# RSD_M1_HELMET_UNIT_MCU_V2.net
KiCad netlist of a schematic drawn in Altium Designer
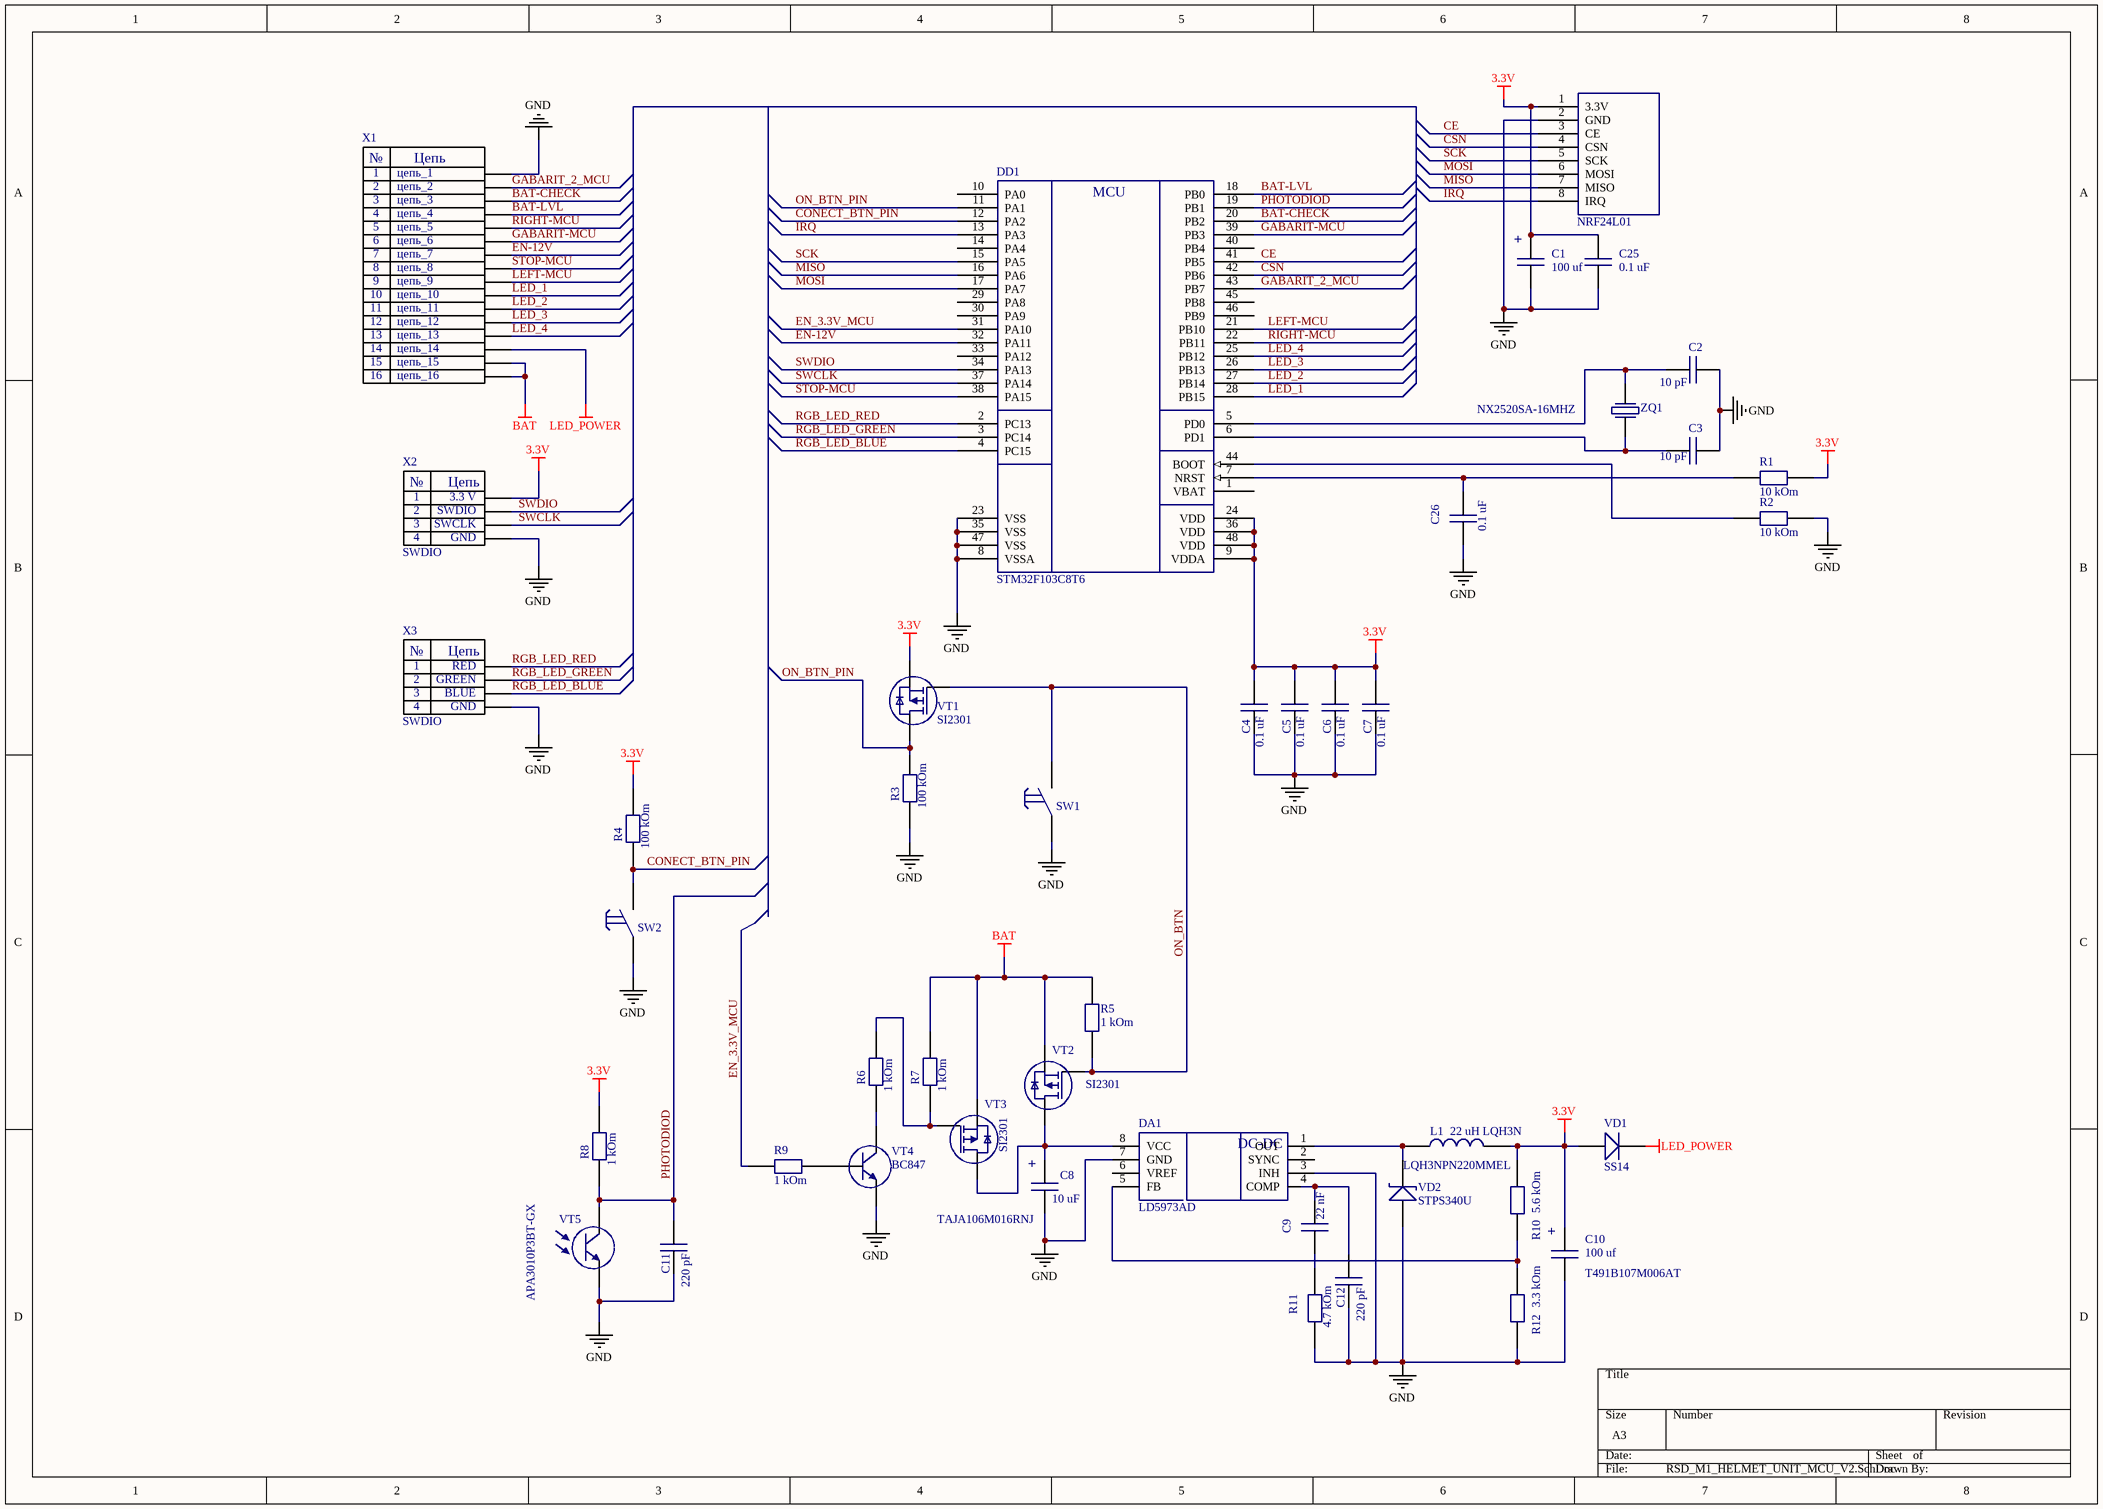
[diagram p0: RSD_M1_HELMET_UNIT_MCU_V2.SchDoc]

(export (version "E")
  (design (tool "Eeschema 10.0.6"))
  (components
    (comp (ref "C1")
      (value "100 uf")
      (footprint "tantal_case_B")
      (libsource (lib "my_library") (part "Capacitor_Polar"))
    )
    (comp (ref "C2")
      (value "10 pF")
      (footprint "CAP0603")
      (fields (field (name "Comment") "Capacitor"))
      (libsource (lib "my_library") (part "Capacitor"))
    )
    (comp (ref "C3")
      (value "10 pF")
      (footprint "CAP0603")
      (fields (field (name "Comment") "Capacitor"))
      (libsource (lib "my_library") (part "Capacitor"))
    )
    (comp (ref "C4")
      (value "0.1 uF")
      (footprint "CAP0603")
      (fields (field (name "Comment") "Capacitor"))
      (libsource (lib "my_library") (part "Capacitor"))
    )
    (comp (ref "C5")
      (value "0.1 uF")
      (footprint "CAP0603")
      (fields (field (name "Comment") "Capacitor"))
      (libsource (lib "my_library") (part "Capacitor"))
    )
    (comp (ref "C6")
      (value "0.1 uF")
      (footprint "CAP0603")
      (fields (field (name "Comment") "Capacitor"))
      (libsource (lib "my_library") (part "Capacitor"))
    )
    (comp (ref "C7")
      (value "0.1 uF")
      (footprint "CAP0603")
      (fields (field (name "Comment") "Capacitor"))
      (libsource (lib "my_library") (part "Capacitor"))
    )
    (comp (ref "C8")
      (value "10 uF")
      (footprint "tantal_case_A")
      (fields (field (name "ALTIUM_VALUE") "TAJA106M016RNJ"))
      (libsource (lib "my_library") (part "Capacitor_Polar"))
    )
    (comp (ref "C9")
      (value "22 nF")
      (footprint "CAP0603")
      (fields (field (name "Comment") "Capacitor"))
      (libsource (lib "my_library") (part "Capacitor"))
    )
    (comp (ref "C10")
      (value "100 uf")
      (footprint "tantal_case_B")
      (fields (field (name "ALTIUM_VALUE") "T491B107M006AT"))
      (libsource (lib "my_library") (part "Capacitor_Polar"))
    )
    (comp (ref "C11")
      (value "220 pF")
      (footprint "CAP0603")
      (fields (field (name "Comment") "Capacitor"))
      (libsource (lib "my_library") (part "Capacitor"))
    )
    (comp (ref "C12")
      (value "220 pF")
      (footprint "CAP0603")
      (fields (field (name "Comment") "Capacitor"))
      (libsource (lib "my_library") (part "Capacitor"))
    )
    (comp (ref "C25")
      (value "0.1 uF")
      (footprint "CAP0603")
      (fields (field (name "Comment") "Capacitor"))
      (libsource (lib "my_library") (part "Capacitor"))
    )
    (comp (ref "C26")
      (value "0.1 uF")
      (footprint "CAP0603")
      (fields (field (name "Comment") "Capacitor"))
      (libsource (lib "my_library") (part "Capacitor"))
    )
    (comp (ref "DA1")
      (value "LD5973AD")
      (footprint "SOIC-8")
      (libsource (lib "my_library") (part "LD5973AD"))
    )
    (comp (ref "DD1")
      (value "STM32F103C8T6")
      (footprint "STM32F103C8T6")
      (fields (field (name "Comment") "STM32F103C8Tx"))
      (libsource (lib "my_library") (part "STM32F103C8Tx"))
    )
    (comp (ref "L1")
      (value "22 uH LQH3N")
      (footprint "LQH3N")
      (fields (field (name "PN") "LQH3NPN220MMEL") (field (name "Comment") "coil"))
      (libsource (lib "my_library") (part "coil"))
    )
    (comp (ref "NRF1")
      (value "NRF24L01")
      (footprint "NRF24L01")
      (libsource (lib "my_library") (part "NRF24L01"))
    )
    (comp (ref "R1")
      (value "10 kOm")
      (footprint "Res0603")
      (fields (field (name "Comment") "Resistor"))
      (libsource (lib "my_library") (part "Resistor"))
    )
    (comp (ref "R2")
      (value "10 kOm")
      (footprint "Res0603")
      (fields (field (name "Comment") "Resistor"))
      (libsource (lib "my_library") (part "Resistor"))
    )
    (comp (ref "R3")
      (value "100 kOm")
      (footprint "Res0603")
      (fields (field (name "Comment") "Resistor"))
      (libsource (lib "my_library") (part "Resistor"))
    )
    (comp (ref "R4")
      (value "100 kOm")
      (footprint "Res0603")
      (fields (field (name "Comment") "Resistor"))
      (libsource (lib "my_library") (part "Resistor"))
    )
    (comp (ref "R5")
      (value "1 kOm")
      (footprint "Res0603")
      (fields (field (name "Comment") "Resistor"))
      (libsource (lib "my_library") (part "Resistor"))
    )
    (comp (ref "R6")
      (value "1 kOm")
      (footprint "Res0603")
      (fields (field (name "Comment") "Resistor"))
      (libsource (lib "my_library") (part "Resistor"))
    )
    (comp (ref "R7")
      (value "1 kOm")
      (footprint "Res0603")
      (fields (field (name "Comment") "Resistor"))
      (libsource (lib "my_library") (part "Resistor"))
    )
    (comp (ref "R8")
      (value "1 kOm")
      (footprint "Res0603")
      (fields (field (name "Comment") "Resistor"))
      (libsource (lib "my_library") (part "Resistor"))
    )
    (comp (ref "R9")
      (value "1 kOm")
      (footprint "Res0603")
      (fields (field (name "Comment") "Resistor"))
      (libsource (lib "my_library") (part "Resistor"))
    )
    (comp (ref "R10")
      (value "5.6 kOm")
      (footprint "Res0603")
      (fields (field (name "Comment") "Resistor"))
      (libsource (lib "my_library") (part "Resistor"))
    )
    (comp (ref "R11")
      (value "4.7 kOm")
      (footprint "Res0603")
      (fields (field (name "Comment") "Resistor"))
      (libsource (lib "my_library") (part "Resistor"))
    )
    (comp (ref "R12")
      (value "3.3 kOm")
      (footprint "Res0603")
      (fields (field (name "Comment") "Resistor"))
      (libsource (lib "my_library") (part "Resistor"))
    )
    (comp (ref "SW1")
      (value "tact_switch")
      (footprint "tact_switch")
      (libsource (lib "my_library") (part "tact_switch"))
    )
    (comp (ref "SW2")
      (value "tact_switch")
      (footprint "tact_switch")
      (libsource (lib "my_library") (part "tact_switch"))
    )
    (comp (ref "VD1")
      (value "SS14")
      (footprint "SMA-F")
      (fields (field (name "Comment") "Diode"))
      (libsource (lib "my_library") (part "Diode"))
    )
    (comp (ref "VD2")
      (value "STPS340U")
      (footprint "SMB1")
      (fields (field (name "Comment") "Schottky"))
      (libsource (lib "my_library") (part "Schottky"))
    )
    (comp (ref "VT1")
      (value "SI2301")
      (footprint "SOT 23")
      (fields (field (name "Comment") "MOSFET-P"))
      (libsource (lib "my_library") (part "MOSFET-P"))
    )
    (comp (ref "VT2")
      (value "SI2301")
      (footprint "SOT 23")
      (fields (field (name "Comment") "MOSFET-P"))
      (libsource (lib "my_library") (part "MOSFET-P"))
    )
    (comp (ref "VT3")
      (value "SI2301")
      (footprint "SOT 23")
      (fields (field (name "Comment") "MOSFET-P"))
      (libsource (lib "my_library") (part "MOSFET-P"))
    )
    (comp (ref "VT4")
      (value "BC847")
      (footprint "SOT 23")
      (fields (field (name "Comment") "NPN"))
      (libsource (lib "my_library") (part "NPN"))
    )
    (comp (ref "VT5")
      (value "APA3010P3BT-GX")
      (footprint "LED0805")
      (fields (field (name "Comment") "Phototransistor"))
      (libsource (lib "my_library") (part "Phototransistor"))
    )
    (comp (ref "X1")
      (value "FPC_connector_16")
      (footprint "FPC_16_0.5")
      (fields
        (field (name "16") "цепь_16")
        (field (name "1") "цепь_1")
        (field (name "2") "цепь_2")
        (field (name "3") "цепь_3")
        (field (name "4") "цепь_4")
        (field (name "5") "цепь_5")
        (field (name "6") "цепь_6")
        (field (name "7") "цепь_7")
        (field (name "8") "цепь_8")
        (field (name "9") "цепь_9")
        (field (name "10") "цепь_10")
        (field (name "11") "цепь_11")
        (field (name "12") "цепь_12")
        (field (name "13") "цепь_13")
        (field (name "14") "цепь_14")
        (field (name "15") "цепь_15")
      )
      (libsource (lib "my_library") (part "FPC_connector_16"))
    )
    (comp (ref "X2")
      (value "SWDIO")
      (footprint "SWDIO")
      (fields
        (field (name "1") "3.3 V")
        (field (name "2") "SWDIO")
        (field (name "3") "SWCLK")
        (field (name "4") "GND")
      )
      (libsource (lib "my_library") (part "SWDIO"))
    )
    (comp (ref "X3")
      (value "SWDIO")
      (footprint "SWDIO")
      (fields
        (field (name "1") "RED")
        (field (name "2") "GREEN")
        (field (name "3") "BLUE")
        (field (name "4") "GND")
      )
      (libsource (lib "my_library") (part "SWDIO"))
    )
    (comp (ref "ZQ1")
      (value "NX2520SA-16MHZ")
      (footprint "crystal")
      (fields (field (name "Comment") "Qartz"))
      (libsource (lib "my_library") (part "Qartz"))
    )
  )
  (nets
    (net (code "1") (name "/BAT-CHECK") (class "Default")
      (node (ref "DD1") (pin "20") (pinfunction "PB2_20") (pintype "passive"))
      (node (ref "X1") (pin "3") (pinfunction "3_3") (pintype "passive"))
    )
    (net (code "2") (name "/BAT-LVL") (class "Default")
      (node (ref "DD1") (pin "18") (pinfunction "PB0_18") (pintype "passive"))
      (node (ref "X1") (pin "4") (pinfunction "4_4") (pintype "passive"))
    )
    (net (code "3") (name "/CE") (class "Default")
      (node (ref "DD1") (pin "41") (pinfunction "PB5_41") (pintype "passive"))
      (node (ref "NRF1") (pin "3") (pinfunction "CE_3") (pintype "passive"))
    )
    (net (code "4") (name "/CONECT_BTN_PIN") (class "Default")
      (node (ref "DD1") (pin "12") (pinfunction "PA2_12") (pintype "passive"))
      (node (ref "R4") (pin "2") (pinfunction "2_2") (pintype "passive"))
      (node (ref "SW2") (pin "2") (pinfunction "2_2") (pintype "passive"))
    )
    (net (code "5") (name "/CSN") (class "Default")
      (node (ref "DD1") (pin "42") (pinfunction "PB6_42") (pintype "passive"))
      (node (ref "NRF1") (pin "4") (pinfunction "CSN_4") (pintype "passive"))
    )
    (net (code "6") (name "/EN-12V") (class "Default")
      (node (ref "DD1") (pin "32") (pinfunction "PA11_32") (pintype "passive"))
      (node (ref "X1") (pin "7") (pinfunction "7_7") (pintype "passive"))
    )
    (net (code "7") (name "/EN_3.3V_MCU") (class "Default")
      (node (ref "DD1") (pin "31") (pinfunction "PA10_31") (pintype "passive"))
      (node (ref "R9") (pin "2") (pinfunction "2_2") (pintype "passive"))
    )
    (net (code "8") (name "/GABARIT-MCU") (class "Default")
      (node (ref "DD1") (pin "39") (pinfunction "PB3_39") (pintype "passive"))
      (node (ref "X1") (pin "6") (pinfunction "6_6") (pintype "passive"))
    )
    (net (code "9") (name "/GABARIT_2_MCU") (class "Default")
      (node (ref "DD1") (pin "43") (pinfunction "PB7_43") (pintype "passive"))
      (node (ref "X1") (pin "2") (pinfunction "2_2") (pintype "passive"))
    )
    (net (code "10") (name "/IRQ") (class "Default")
      (node (ref "DD1") (pin "13") (pinfunction "PA3_13") (pintype "passive"))
      (node (ref "NRF1") (pin "8") (pinfunction "IRQ_8") (pintype "passive"))
    )
    (net (code "11") (name "/LED_1") (class "Default")
      (node (ref "DD1") (pin "28") (pinfunction "PB15_28") (pintype "passive"))
      (node (ref "X1") (pin "10") (pinfunction "10_10") (pintype "passive"))
    )
    (net (code "12") (name "/LED_2") (class "Default")
      (node (ref "DD1") (pin "27") (pinfunction "PB14_27") (pintype "passive"))
      (node (ref "X1") (pin "11") (pinfunction "11_11") (pintype "passive"))
    )
    (net (code "13") (name "/LED_3") (class "Default")
      (node (ref "DD1") (pin "26") (pinfunction "PB13_26") (pintype "passive"))
      (node (ref "X1") (pin "12") (pinfunction "12_12") (pintype "passive"))
    )
    (net (code "14") (name "/LED_4") (class "Default")
      (node (ref "DD1") (pin "25") (pinfunction "PB12_25") (pintype "passive"))
      (node (ref "X1") (pin "13") (pinfunction "13_13") (pintype "passive"))
    )
    (net (code "15") (name "/LEFT-MCU") (class "Default")
      (node (ref "DD1") (pin "21") (pinfunction "PB10_21") (pintype "passive"))
      (node (ref "X1") (pin "9") (pinfunction "9_9") (pintype "passive"))
    )
    (net (code "16") (name "/MISO") (class "Default")
      (node (ref "DD1") (pin "16") (pinfunction "PA6_16") (pintype "passive"))
      (node (ref "NRF1") (pin "7") (pinfunction "MISO_7") (pintype "passive"))
    )
    (net (code "17") (name "/MOSI") (class "Default")
      (node (ref "DD1") (pin "17") (pinfunction "PA7_17") (pintype "passive"))
      (node (ref "NRF1") (pin "6") (pinfunction "MOSI_6") (pintype "passive"))
    )
    (net (code "18") (name "/ON_BTN") (class "Default")
      (node (ref "R5") (pin "1") (pinfunction "1_1") (pintype "passive"))
      (node (ref "SW1") (pin "2") (pinfunction "2_2") (pintype "passive"))
      (node (ref "VT1") (pin "G") (pintype "passive"))
      (node (ref "VT2") (pin "G") (pintype "passive"))
    )
    (net (code "19") (name "/ON_BTN_PIN") (class "Default")
      (node (ref "DD1") (pin "11") (pinfunction "PA1_11") (pintype "passive"))
      (node (ref "R3") (pin "1") (pinfunction "1_1") (pintype "passive"))
      (node (ref "VT1") (pin "D") (pintype "passive"))
    )
    (net (code "20") (name "/PHOTODIOD") (class "Default")
      (node (ref "C11") (pin "2") (pinfunction "2_2") (pintype "passive"))
      (node (ref "DD1") (pin "19") (pinfunction "PB1_19") (pintype "passive"))
      (node (ref "R8") (pin "1") (pinfunction "1_1") (pintype "passive"))
      (node (ref "VT5") (pin "1") (pinfunction "1_1") (pintype "passive"))
    )
    (net (code "21") (name "/RGB_LED_BLUE") (class "Default")
      (node (ref "DD1") (pin "4") (pinfunction "PC15_4") (pintype "passive"))
      (node (ref "X3") (pin "3") (pinfunction "3_3") (pintype "passive"))
    )
    (net (code "22") (name "/RGB_LED_GREEN") (class "Default")
      (node (ref "DD1") (pin "3") (pinfunction "PC14_3") (pintype "passive"))
      (node (ref "X3") (pin "2") (pinfunction "2_2") (pintype "passive"))
    )
    (net (code "23") (name "/RGB_LED_RED") (class "Default")
      (node (ref "DD1") (pin "2") (pinfunction "PC13_2") (pintype "passive"))
      (node (ref "X3") (pin "1") (pinfunction "1_1") (pintype "passive"))
    )
    (net (code "24") (name "/RIGHT-MCU") (class "Default")
      (node (ref "DD1") (pin "22") (pinfunction "PB11_22") (pintype "passive"))
      (node (ref "X1") (pin "5") (pinfunction "5_5") (pintype "passive"))
    )
    (net (code "25") (name "/SCK") (class "Default")
      (node (ref "DD1") (pin "15") (pinfunction "PA5_15") (pintype "passive"))
      (node (ref "NRF1") (pin "5") (pinfunction "SCK_5") (pintype "passive"))
    )
    (net (code "26") (name "/STOP-MCU") (class "Default")
      (node (ref "DD1") (pin "38") (pinfunction "PA15_38") (pintype "passive"))
      (node (ref "X1") (pin "8") (pinfunction "8_8") (pintype "passive"))
    )
    (net (code "27") (name "/SWCLK") (class "Default")
      (node (ref "DD1") (pin "37") (pinfunction "PA14_37") (pintype "passive"))
      (node (ref "X2") (pin "3") (pinfunction "3_3") (pintype "passive"))
    )
    (net (code "28") (name "/SWDIO") (class "Default")
      (node (ref "DD1") (pin "34") (pinfunction "PA13_34") (pintype "passive"))
      (node (ref "X2") (pin "2") (pinfunction "2_2") (pintype "passive"))
    )
    (net (code "29") (name "3.3V") (class "Default")
      (node (ref "C1") (pin "1") (pinfunction "1_1") (pintype "passive"))
      (node (ref "C10") (pin "1") (pinfunction "1_1") (pintype "passive"))
      (node (ref "C25") (pin "2") (pinfunction "2_2") (pintype "passive"))
      (node (ref "C4") (pin "2") (pinfunction "2_2") (pintype "passive"))
      (node (ref "C5") (pin "2") (pinfunction "2_2") (pintype "passive"))
      (node (ref "C6") (pin "2") (pinfunction "2_2") (pintype "passive"))
      (node (ref "C7") (pin "2") (pinfunction "2_2") (pintype "passive"))
      (node (ref "DD1") (pin "24") (pinfunction "VDD_24") (pintype "passive"))
      (node (ref "DD1") (pin "36") (pinfunction "VDD_36") (pintype "passive"))
      (node (ref "DD1") (pin "48") (pinfunction "VDD_48") (pintype "passive"))
      (node (ref "DD1") (pin "9") (pinfunction "VDDA_9") (pintype "passive"))
      (node (ref "L1") (pin "2") (pinfunction "2_2") (pintype "passive"))
      (node (ref "NRF1") (pin "1") (pinfunction "3.3V_1") (pintype "passive"))
      (node (ref "R1") (pin "2") (pinfunction "2_2") (pintype "passive"))
      (node (ref "R10") (pin "1") (pinfunction "1_1") (pintype "passive"))
      (node (ref "R4") (pin "1") (pinfunction "1_1") (pintype "passive"))
      (node (ref "R8") (pin "2") (pinfunction "2_2") (pintype "passive"))
      (node (ref "VD1") (pin "2") (pinfunction "2_2") (pintype "passive"))
      (node (ref "VT1") (pin "S") (pintype "passive"))
      (node (ref "X2") (pin "1") (pinfunction "1_1") (pintype "passive"))
    )
    (net (code "30") (name "BAT") (class "Default")
      (node (ref "R5") (pin "2") (pinfunction "2_2") (pintype "passive"))
      (node (ref "R7") (pin "2") (pinfunction "2_2") (pintype "passive"))
      (node (ref "VT2") (pin "S") (pintype "passive"))
      (node (ref "VT3") (pin "S") (pintype "passive"))
      (node (ref "X1") (pin "15") (pinfunction "15_15") (pintype "passive"))
      (node (ref "X1") (pin "16") (pinfunction "16_16") (pintype "passive"))
    )
    (net (code "31") (name "GND") (class "Default")
      (node (ref "C1") (pin "2") (pinfunction "2_2") (pintype "passive"))
      (node (ref "C10") (pin "2") (pinfunction "2_2") (pintype "passive"))
      (node (ref "C11") (pin "1") (pinfunction "1_1") (pintype "passive"))
      (node (ref "C12") (pin "1") (pinfunction "1_1") (pintype "passive"))
      (node (ref "C2") (pin "1") (pinfunction "1_1") (pintype "passive"))
      (node (ref "C25") (pin "1") (pinfunction "1_1") (pintype "passive"))
      (node (ref "C26") (pin "1") (pinfunction "1_1") (pintype "passive"))
      (node (ref "C3") (pin "1") (pinfunction "1_1") (pintype "passive"))
      (node (ref "C4") (pin "1") (pinfunction "1_1") (pintype "passive"))
      (node (ref "C5") (pin "1") (pinfunction "1_1") (pintype "passive"))
      (node (ref "C6") (pin "1") (pinfunction "1_1") (pintype "passive"))
      (node (ref "C7") (pin "1") (pinfunction "1_1") (pintype "passive"))
      (node (ref "C8") (pin "2") (pinfunction "2_2") (pintype "passive"))
      (node (ref "DA1") (pin "3") (pinfunction "INH_3") (pintype "passive"))
      (node (ref "DA1") (pin "7") (pinfunction "GND_7") (pintype "passive"))
      (node (ref "DD1") (pin "23") (pinfunction "VSS_23") (pintype "passive"))
      (node (ref "DD1") (pin "35") (pinfunction "VSS_35") (pintype "passive"))
      (node (ref "DD1") (pin "47") (pinfunction "VSS_47") (pintype "passive"))
      (node (ref "DD1") (pin "8") (pinfunction "VSSA_8") (pintype "passive"))
      (node (ref "NRF1") (pin "2") (pinfunction "GND_2") (pintype "passive"))
      (node (ref "R11") (pin "2") (pinfunction "2_2") (pintype "passive"))
      (node (ref "R12") (pin "2") (pinfunction "2_2") (pintype "passive"))
      (node (ref "R2") (pin "2") (pinfunction "2_2") (pintype "passive"))
      (node (ref "R3") (pin "2") (pinfunction "2_2") (pintype "passive"))
      (node (ref "SW1") (pin "1") (pinfunction "1_1") (pintype "passive"))
      (node (ref "SW2") (pin "1") (pinfunction "1_1") (pintype "passive"))
      (node (ref "VD2") (pin "2") (pinfunction "2_2") (pintype "passive"))
      (node (ref "VT4") (pin "E") (pinfunction "E_E") (pintype "passive"))
      (node (ref "VT5") (pin "2") (pinfunction "2_2") (pintype "passive"))
      (node (ref "X1") (pin "1") (pinfunction "1_1") (pintype "passive"))
      (node (ref "X2") (pin "4") (pinfunction "4_4") (pintype "passive"))
      (node (ref "X3") (pin "4") (pinfunction "4_4") (pintype "passive"))
    )
    (net (code "32") (name "LED_POWER") (class "Default")
      (node (ref "VD1") (pin "1") (pinfunction "1_1") (pintype "passive"))
      (node (ref "X1") (pin "14") (pinfunction "14_14") (pintype "passive"))
    )
    (net (code "33") (name "Net-(C9-Pad1)") (class "Default")
      (node (ref "C9") (pin "1") (pinfunction "1_1") (pintype "passive"))
      (node (ref "R11") (pin "1") (pinfunction "1_1") (pintype "passive"))
    )
    (net (code "34") (name "Net-(DA1-COMP)") (class "Default")
      (node (ref "C12") (pin "2") (pinfunction "2_2") (pintype "passive"))
      (node (ref "C9") (pin "2") (pinfunction "2_2") (pintype "passive"))
      (node (ref "DA1") (pin "4") (pinfunction "COMP_4") (pintype "passive"))
    )
    (net (code "35") (name "Net-(DA1-FB)") (class "Default")
      (node (ref "DA1") (pin "5") (pinfunction "FB_5") (pintype "passive"))
      (node (ref "R10") (pin "2") (pinfunction "2_2") (pintype "passive"))
      (node (ref "R12") (pin "1") (pinfunction "1_1") (pintype "passive"))
    )
    (net (code "36") (name "Net-(DA1-OUT)") (class "Default")
      (node (ref "DA1") (pin "1") (pinfunction "OUT_1") (pintype "passive"))
      (node (ref "L1") (pin "1") (pinfunction "1_1") (pintype "passive"))
      (node (ref "VD2") (pin "1") (pinfunction "1_1") (pintype "passive"))
    )
    (net (code "37") (name "Net-(DA1-VCC)") (class "Default")
      (node (ref "C8") (pin "1") (pinfunction "1_1") (pintype "passive"))
      (node (ref "DA1") (pin "8") (pinfunction "VCC_8") (pintype "passive"))
      (node (ref "VT2") (pin "D") (pintype "passive"))
      (node (ref "VT3") (pin "D") (pintype "passive"))
    )
    (net (code "38") (name "Net-(DD1-BOOT)") (class "Default")
      (node (ref "DD1") (pin "44") (pinfunction "BOOT_44") (pintype "input"))
      (node (ref "R2") (pin "1") (pinfunction "1_1") (pintype "passive"))
    )
    (net (code "39") (name "Net-(DD1-NRST)") (class "Default")
      (node (ref "C26") (pin "2") (pinfunction "2_2") (pintype "passive"))
      (node (ref "DD1") (pin "7") (pinfunction "NRST_7") (pintype "input"))
      (node (ref "R1") (pin "1") (pinfunction "1_1") (pintype "passive"))
    )
    (net (code "40") (name "Net-(DD1-PD0)") (class "Default")
      (node (ref "C2") (pin "2") (pinfunction "2_2") (pintype "passive"))
      (node (ref "DD1") (pin "5") (pinfunction "PD0_5") (pintype "passive"))
      (node (ref "ZQ1") (pin "2") (pinfunction "2_2") (pintype "passive"))
    )
    (net (code "41") (name "Net-(DD1-PD1)") (class "Default")
      (node (ref "C3") (pin "2") (pinfunction "2_2") (pintype "passive"))
      (node (ref "DD1") (pin "6") (pinfunction "PD1_6") (pintype "passive"))
      (node (ref "ZQ1") (pin "1") (pinfunction "1_1") (pintype "passive"))
    )
    (net (code "42") (name "Net-(R6-Pad1)") (class "Default")
      (node (ref "R6") (pin "1") (pinfunction "1_1") (pintype "passive"))
      (node (ref "VT4") (pin "K") (pinfunction "K_K") (pintype "passive"))
    )
    (net (code "43") (name "Net-(R6-Pad2)") (class "Default")
      (node (ref "R6") (pin "2") (pinfunction "2_2") (pintype "passive"))
      (node (ref "R7") (pin "1") (pinfunction "1_1") (pintype "passive"))
      (node (ref "VT3") (pin "G") (pintype "passive"))
    )
    (net (code "44") (name "Net-(R9-Pad1)") (class "Default")
      (node (ref "R9") (pin "1") (pinfunction "1_1") (pintype "passive"))
      (node (ref "VT4") (pin "B") (pinfunction "B_B") (pintype "passive"))
    )
    (net (code "45") (name "unconnected-(DA1-SYNC-Pad2)") (class "Default")
      (node (ref "DA1") (pin "2") (pinfunction "SYNC_2") (pintype "passive"))
    )
    (net (code "46") (name "unconnected-(DA1-VREF-Pad6)") (class "Default")
      (node (ref "DA1") (pin "6") (pinfunction "VREF_6") (pintype "passive"))
    )
    (net (code "47") (name "unconnected-(DD1-PA0-Pad10)") (class "Default")
      (node (ref "DD1") (pin "10") (pinfunction "PA0_10") (pintype "passive"))
    )
    (net (code "48") (name "unconnected-(DD1-PA4-Pad14)") (class "Default")
      (node (ref "DD1") (pin "14") (pinfunction "PA4_14") (pintype "passive"))
    )
    (net (code "49") (name "unconnected-(DD1-PA8-Pad29)") (class "Default")
      (node (ref "DD1") (pin "29") (pinfunction "PA8_29") (pintype "passive"))
    )
    (net (code "50") (name "unconnected-(DD1-PA9-Pad30)") (class "Default")
      (node (ref "DD1") (pin "30") (pinfunction "PA9_30") (pintype "passive"))
    )
    (net (code "51") (name "unconnected-(DD1-PA12-Pad33)") (class "Default")
      (node (ref "DD1") (pin "33") (pinfunction "PA12_33") (pintype "passive"))
    )
    (net (code "52") (name "unconnected-(DD1-PB4-Pad40)") (class "Default")
      (node (ref "DD1") (pin "40") (pinfunction "PB4_40") (pintype "passive"))
    )
    (net (code "53") (name "unconnected-(DD1-PB8-Pad45)") (class "Default")
      (node (ref "DD1") (pin "45") (pinfunction "PB8_45") (pintype "passive"))
    )
    (net (code "54") (name "unconnected-(DD1-PB9-Pad46)") (class "Default")
      (node (ref "DD1") (pin "46") (pinfunction "PB9_46") (pintype "passive"))
    )
    (net (code "55") (name "unconnected-(DD1-VBAT-Pad1)") (class "Default")
      (node (ref "DD1") (pin "1") (pinfunction "VBAT_1") (pintype "passive"))
    )
  )
)
